# speedmeter_3_3reg.net
KiCad netlist of a schematic drawn in EAGLE
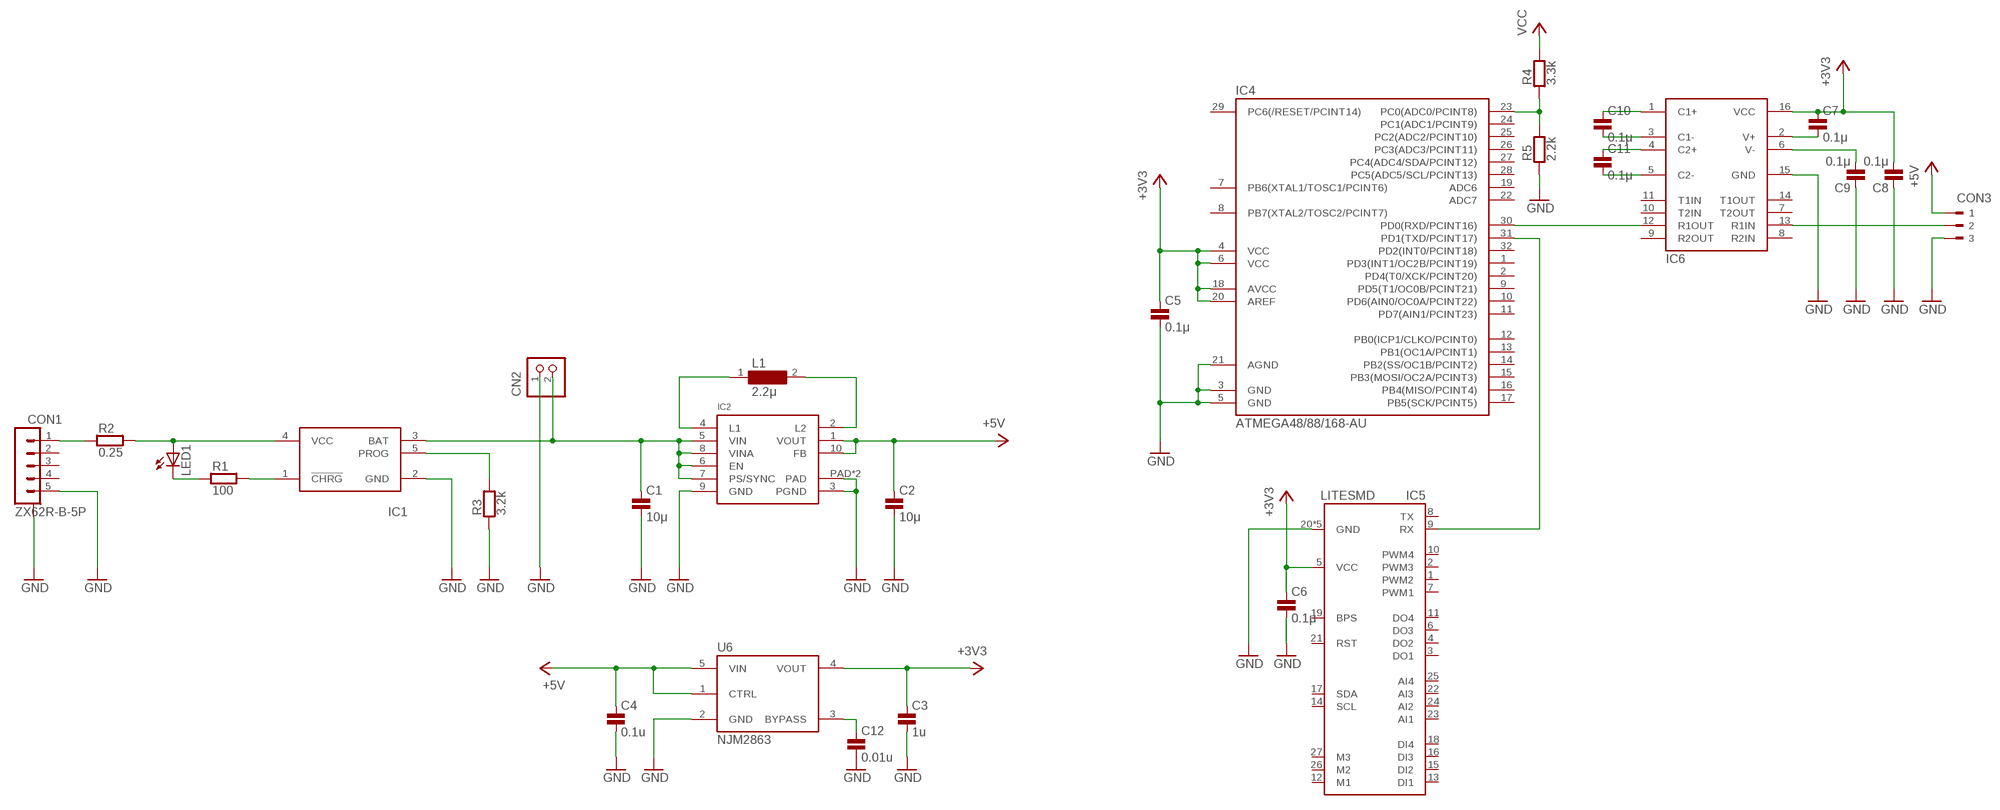
[diagram p0: schematic, sheet 1]

(export (version "E")
  (design (tool "Eeschema 10.0.6"))
  (components
    (comp (ref "C1")
      (value "10μ")
      (footprint "eagle-import:0603@1")
      (libsource (lib "eagle-import") (part "C0603"))
    )
    (comp (ref "C2")
      (value "10μ")
      (footprint "eagle-import:0603@1")
      (libsource (lib "eagle-import") (part "C0603"))
    )
    (comp (ref "C3")
      (value "1u")
      (footprint "eagle-import:0603@1")
      (libsource (lib "eagle-import") (part "C0603"))
    )
    (comp (ref "C4")
      (value "0.1u")
      (footprint "eagle-import:0603@1")
      (libsource (lib "eagle-import") (part "C0603"))
    )
    (comp (ref "C5")
      (value "0.1μ")
      (footprint "eagle-import:0603@1")
      (libsource (lib "eagle-import") (part "C0603"))
    )
    (comp (ref "C6")
      (value "0.1μ")
      (footprint "eagle-import:0603@1")
      (libsource (lib "eagle-import") (part "C0603"))
    )
    (comp (ref "C7")
      (value "0.1μ")
      (footprint "eagle-import:0603")
      (libsource (lib "eagle-import") (part "untitled-2_C0603"))
    )
    (comp (ref "C8")
      (value "0.1μ")
      (footprint "eagle-import:0603")
      (libsource (lib "eagle-import") (part "untitled-2_C0603"))
    )
    (comp (ref "C9")
      (value "0.1μ")
      (footprint "eagle-import:0603")
      (libsource (lib "eagle-import") (part "untitled-2_C0603"))
    )
    (comp (ref "C10")
      (value "0.1μ")
      (footprint "eagle-import:0603")
      (libsource (lib "eagle-import") (part "untitled-2_C0603"))
    )
    (comp (ref "C11")
      (value "0.1μ")
      (footprint "eagle-import:0603")
      (libsource (lib "eagle-import") (part "untitled-2_C0603"))
    )
    (comp (ref "C12")
      (value "0.01u")
      (footprint "eagle-import:0603@1")
      (libsource (lib "eagle-import") (part "C0603"))
    )
    (comp (ref "CN2")
      (value "S2B-PH-K-S")
      (footprint "eagle-import:S2B-PH-K-S")
      (libsource (lib "eagle-import") (part "S2B-PH-K-S"))
    )
    (comp (ref "CON1")
      (value "ZX62R-B-5P")
      (footprint "eagle-import:MICRO-B")
      (libsource (lib "eagle-import") (part "ZX62R-B-5P"))
    )
    (comp (ref "CON3")
      (value "180-3")
      (footprint "eagle-import:180-3")
      (libsource (lib "eagle-import") (part "180-3"))
    )
    (comp (ref "IC1")
      (value "LTC4054")
      (footprint "eagle-import:TSOT23-5")
      (libsource (lib "eagle-import") (part "LTC4054"))
    )
    (comp (ref "IC2")
      (value "TPS6300XDRCT")
      (footprint "eagle-import:S-PVSON-N10")
      (libsource (lib "eagle-import") (part "TPS6300XDRCT"))
    )
    (comp (ref "IC4")
      (value "ATMEGA48/88/168-AU")
      (footprint "eagle-import:TQFP32-08")
      (libsource (lib "eagle-import") (part "ATMEGA48/88/168-AU"))
    )
    (comp (ref "IC5")
      (value "LITESMD")
      (footprint "eagle-import:LITE")
      (libsource (lib "eagle-import") (part "LITESMD"))
    )
    (comp (ref "IC6")
      (value "ADM3202ARN")
      (footprint "eagle-import:SOP16")
      (libsource (lib "eagle-import") (part "ADM3202ARN"))
    )
    (comp (ref "L1")
      (value "2.2μ")
      (footprint "eagle-import:VLF4012ST")
      (libsource (lib "eagle-import") (part "VLF4012ST"))
    )
    (comp (ref "LED1")
      (value "LEDSML0603")
      (footprint "eagle-import:SML0603")
      (libsource (lib "eagle-import") (part "LEDSML0603"))
    )
    (comp (ref "R1")
      (value "100")
      (footprint "eagle-import:0603")
      (libsource (lib "eagle-import") (part "R0603"))
    )
    (comp (ref "R2")
      (value "0.25")
      (footprint "eagle-import:0603")
      (libsource (lib "eagle-import") (part "R0603"))
    )
    (comp (ref "R3")
      (value "3.2k")
      (footprint "eagle-import:0603")
      (libsource (lib "eagle-import") (part "R0603"))
    )
    (comp (ref "R4")
      (value "3.3k")
      (footprint "eagle-import:0603")
      (libsource (lib "eagle-import") (part "R0603"))
    )
    (comp (ref "R5")
      (value "2.2k")
      (footprint "eagle-import:0603")
      (libsource (lib "eagle-import") (part "R0603"))
    )
    (comp (ref "U6")
      (value "NJM2863")
      (footprint "eagle-import:SOT23_5PIN")
      (libsource (lib "eagle-import") (part "NJM2863"))
    )
  )
  (nets
    (net (code "1") (name "+3V3") (class "Default")
      (node (ref "C3") (pin "1") (pinfunction "P$1_1") (pintype "passive"))
      (node (ref "C5") (pin "1") (pinfunction "P$1_1") (pintype "passive"))
      (node (ref "C6") (pin "1") (pinfunction "P$1_1") (pintype "passive"))
      (node (ref "C7") (pin "1") (pinfunction "P$1_1") (pintype "passive"))
      (node (ref "C8") (pin "2") (pinfunction "P$2_2") (pintype "passive"))
      (node (ref "IC4") (pin "18") (pinfunction "AVCC_18") (pintype "passive"))
      (node (ref "IC4") (pin "20") (pinfunction "AREF_20") (pintype "passive"))
      (node (ref "IC4") (pin "4") (pinfunction "VCC_4") (pintype "power_in"))
      (node (ref "IC4") (pin "6") (pinfunction "VCC_6") (pintype "power_in"))
      (node (ref "IC5") (pin "5") (pinfunction "VCC_5") (pintype "power_in"))
      (node (ref "IC6") (pin "16") (pinfunction "VCC_16") (pintype "bidirectional"))
      (node (ref "U6") (pin "4") (pinfunction "VOUT_4") (pintype "output"))
    )
    (net (code "2") (name "+5V") (class "Default")
      (node (ref "C2") (pin "1") (pinfunction "P$1_1") (pintype "passive"))
      (node (ref "C4") (pin "1") (pinfunction "P$1_1") (pintype "passive"))
      (node (ref "CON3") (pin "1") (pinfunction "1_1") (pintype "passive"))
      (node (ref "IC2") (pin "1") (pinfunction "VOUT_1") (pintype "output"))
      (node (ref "IC2") (pin "10") (pinfunction "FB_10") (pintype "input"))
      (node (ref "U6") (pin "1") (pinfunction "CTRL_1") (pintype "input"))
      (node (ref "U6") (pin "5") (pinfunction "VIN_5") (pintype "input"))
    )
    (net (code "3") (name "GND") (class "Default")
      (node (ref "C1") (pin "2") (pinfunction "P$2_2") (pintype "passive"))
      (node (ref "C12") (pin "2") (pinfunction "P$2_2") (pintype "passive"))
      (node (ref "C2") (pin "2") (pinfunction "P$2_2") (pintype "passive"))
      (node (ref "C3") (pin "2") (pinfunction "P$2_2") (pintype "passive"))
      (node (ref "C4") (pin "2") (pinfunction "P$2_2") (pintype "passive"))
      (node (ref "C5") (pin "2") (pinfunction "P$2_2") (pintype "passive"))
      (node (ref "C6") (pin "2") (pinfunction "P$2_2") (pintype "passive"))
      (node (ref "C8") (pin "1") (pinfunction "P$1_1") (pintype "passive"))
      (node (ref "C9") (pin "1") (pinfunction "P$1_1") (pintype "passive"))
      (node (ref "CN2") (pin "1") (pinfunction "1_1") (pintype "passive"))
      (node (ref "CON1") (pin "5") (pinfunction "1.VBUS_5") (pintype "passive"))
      (node (ref "CON1") (pin "CASE@1") (pinfunction "P$1_CASE@1") (pintype "bidirectional"))
      (node (ref "CON1") (pin "CASE@2") (pinfunction "P$1_CASE@2") (pintype "bidirectional"))
      (node (ref "CON1") (pin "CASE@3") (pinfunction "P$1_CASE@3") (pintype "bidirectional"))
      (node (ref "CON1") (pin "CASE@4") (pinfunction "P$1_CASE@4") (pintype "bidirectional"))
      (node (ref "CON3") (pin "3") (pinfunction "3_3") (pintype "passive"))
      (node (ref "IC1") (pin "2") (pinfunction "GND_2") (pintype "power_in"))
      (node (ref "IC2") (pin "3") (pinfunction "PGND_3") (pintype "power_in"))
      (node (ref "IC2") (pin "9") (pinfunction "GND_9") (pintype "power_in"))
      (node (ref "IC2") (pin "PAD") (pinfunction "PAD_PAD") (pintype "power_in"))
      (node (ref "IC2") (pin "PAD@1") (pinfunction "PAD_PAD@1") (pintype "power_in"))
      (node (ref "IC4") (pin "21") (pinfunction "AGND_21") (pintype "power_in"))
      (node (ref "IC4") (pin "3") (pinfunction "GND_3") (pintype "power_in"))
      (node (ref "IC4") (pin "5") (pinfunction "GND_5") (pintype "power_in"))
      (node (ref "IC5") (pin "20") (pinfunction "GND_20") (pintype "power_in"))
      (node (ref "IC5") (pin "28") (pinfunction "GND_28") (pintype "power_in"))
      (node (ref "IC5") (pin "30") (pinfunction "GND_30") (pintype "power_in"))
      (node (ref "IC5") (pin "31") (pinfunction "GND_31") (pintype "power_in"))
      (node (ref "IC5") (pin "32") (pinfunction "GND_32") (pintype "power_in"))
      (node (ref "IC6") (pin "15") (pinfunction "GND_15") (pintype "bidirectional"))
      (node (ref "R3") (pin "1") (pinfunction "P$1_1") (pintype "passive"))
      (node (ref "R5") (pin "1") (pinfunction "P$1_1") (pintype "passive"))
      (node (ref "U6") (pin "2") (pinfunction "GND_2") (pintype "power_in"))
    )
    (net (code "4") (name "Net-(C7-P$2)") (class "Default")
      (node (ref "C7") (pin "2") (pinfunction "P$2_2") (pintype "passive"))
      (node (ref "IC6") (pin "2") (pinfunction "V+_2") (pintype "bidirectional"))
    )
    (net (code "5") (name "Net-(C9-P$2)") (class "Default")
      (node (ref "C9") (pin "2") (pinfunction "P$2_2") (pintype "passive"))
      (node (ref "IC6") (pin "6") (pinfunction "V-_6") (pintype "bidirectional"))
    )
    (net (code "6") (name "Net-(C10-P$1)") (class "Default")
      (node (ref "C10") (pin "1") (pinfunction "P$1_1") (pintype "passive"))
      (node (ref "IC6") (pin "1") (pinfunction "C1+_1") (pintype "bidirectional"))
    )
    (net (code "7") (name "Net-(C10-P$2)") (class "Default")
      (node (ref "C10") (pin "2") (pinfunction "P$2_2") (pintype "passive"))
      (node (ref "IC6") (pin "3") (pinfunction "C1-_3") (pintype "bidirectional"))
    )
    (net (code "8") (name "Net-(C11-P$1)") (class "Default")
      (node (ref "C11") (pin "1") (pinfunction "P$1_1") (pintype "passive"))
      (node (ref "IC6") (pin "4") (pinfunction "C2+_4") (pintype "bidirectional"))
    )
    (net (code "9") (name "Net-(C11-P$2)") (class "Default")
      (node (ref "C11") (pin "2") (pinfunction "P$2_2") (pintype "passive"))
      (node (ref "IC6") (pin "5") (pinfunction "C2-_5") (pintype "bidirectional"))
    )
    (net (code "10") (name "Net-(C12-P$1)") (class "Default")
      (node (ref "C12") (pin "1") (pinfunction "P$1_1") (pintype "passive"))
      (node (ref "U6") (pin "3") (pinfunction "BYPASS_3") (pintype "passive"))
    )
    (net (code "11") (name "Net-(CON1-5.GND)") (class "Default")
      (node (ref "CON1") (pin "1") (pinfunction "5.GND_1") (pintype "passive"))
      (node (ref "R2") (pin "1") (pinfunction "P$1_1") (pintype "passive"))
    )
    (net (code "12") (name "Net-(IC1-PROG)") (class "Default")
      (node (ref "IC1") (pin "5") (pinfunction "PROG_5") (pintype "passive"))
      (node (ref "R3") (pin "2") (pinfunction "P$2_2") (pintype "passive"))
    )
    (net (code "13") (name "Net-(IC1-VCC)") (class "Default")
      (node (ref "IC1") (pin "4") (pinfunction "VCC_4") (pintype "power_in"))
      (node (ref "LED1") (pin "A") (pinfunction "A_A") (pintype "passive"))
      (node (ref "R2") (pin "2") (pinfunction "P$2_2") (pintype "passive"))
    )
    (net (code "14") (name "Net-(IC1-~{CHRG})") (class "Default")
      (node (ref "IC1") (pin "1") (pinfunction "~{CHRG}_1") (pintype "output"))
      (node (ref "R1") (pin "2") (pinfunction "P$2_2") (pintype "passive"))
    )
    (net (code "15") (name "Net-(IC2-L1)") (class "Default")
      (node (ref "IC2") (pin "4") (pinfunction "L1_4") (pintype "bidirectional"))
      (node (ref "L1") (pin "1") (pinfunction "1_1") (pintype "passive"))
    )
    (net (code "16") (name "Net-(IC2-L2)") (class "Default")
      (node (ref "IC2") (pin "2") (pinfunction "L2_2") (pintype "bidirectional"))
      (node (ref "L1") (pin "2") (pinfunction "2_2") (pintype "passive"))
    )
    (net (code "17") (name "Net-(IC4-PC0(ADC0{slash}PCINT8))") (class "Default")
      (node (ref "IC4") (pin "23") (pinfunction "PC0(ADC0/PCINT8)_23") (pintype "bidirectional"))
      (node (ref "R4") (pin "1") (pinfunction "P$1_1") (pintype "passive"))
      (node (ref "R5") (pin "2") (pinfunction "P$2_2") (pintype "passive"))
    )
    (net (code "18") (name "Net-(IC4-PD0(RXD{slash}PCINT16))") (class "Default")
      (node (ref "IC4") (pin "30") (pinfunction "PD0(RXD/PCINT16)_30") (pintype "bidirectional"))
      (node (ref "IC6") (pin "12") (pinfunction "R1OUT_12") (pintype "bidirectional"))
    )
    (net (code "19") (name "Net-(IC4-PD1(TXD{slash}PCINT17))") (class "Default")
      (node (ref "IC4") (pin "31") (pinfunction "PD1(TXD/PCINT17)_31") (pintype "bidirectional"))
      (node (ref "IC5") (pin "9") (pinfunction "RX_9") (pintype "input"))
    )
    (net (code "20") (name "Net-(IC6-R1IN)") (class "Default")
      (node (ref "CON3") (pin "2") (pinfunction "2_2") (pintype "passive"))
      (node (ref "IC6") (pin "13") (pinfunction "R1IN_13") (pintype "bidirectional"))
    )
    (net (code "21") (name "Net-(R1-P$1)") (class "Default")
      (node (ref "LED1") (pin "C") (pinfunction "C_C") (pintype "passive"))
      (node (ref "R1") (pin "1") (pinfunction "P$1_1") (pintype "passive"))
    )
    (net (code "22") (name "VCC") (class "Default")
      (node (ref "C1") (pin "1") (pinfunction "P$1_1") (pintype "passive"))
      (node (ref "CN2") (pin "2") (pinfunction "2_2") (pintype "passive"))
      (node (ref "IC1") (pin "3") (pinfunction "BAT_3") (pintype "power_in"))
      (node (ref "IC2") (pin "5") (pinfunction "VIN_5") (pintype "power_in"))
      (node (ref "IC2") (pin "6") (pinfunction "EN_6") (pintype "input"))
      (node (ref "IC2") (pin "7") (pinfunction "PS/SYNC_7") (pintype "input"))
      (node (ref "IC2") (pin "8") (pinfunction "VINA_8") (pintype "power_in"))
      (node (ref "R4") (pin "2") (pinfunction "P$2_2") (pintype "passive"))
    )
    (net (code "23") (name "unconnected-(CON1-2.D--Pad4)") (class "Default")
      (node (ref "CON1") (pin "4") (pinfunction "2.D-_4") (pintype "passive"))
    )
    (net (code "24") (name "unconnected-(CON1-3.D+-Pad3)") (class "Default")
      (node (ref "CON1") (pin "3") (pinfunction "3.D+_3") (pintype "passive"))
    )
    (net (code "25") (name "unconnected-(CON1-4.ID-Pad2)") (class "Default")
      (node (ref "CON1") (pin "2") (pinfunction "4.ID_2") (pintype "passive"))
    )
    (net (code "26") (name "unconnected-(IC4-ADC6-Pad19)") (class "Default")
      (node (ref "IC4") (pin "19") (pinfunction "ADC6_19") (pintype "passive"))
    )
    (net (code "27") (name "unconnected-(IC4-ADC7-Pad22)") (class "Default")
      (node (ref "IC4") (pin "22") (pinfunction "ADC7_22") (pintype "passive"))
    )
    (net (code "28") (name "unconnected-(IC4-PB0(ICP1{slash}CLKO{slash}PCINT0)-Pad12)") (class "Default")
      (node (ref "IC4") (pin "12") (pinfunction "PB0(ICP1/CLKO/PCINT0)_12") (pintype "bidirectional"))
    )
    (net (code "29") (name "unconnected-(IC4-PB1(OC1A{slash}PCINT1)-Pad13)") (class "Default")
      (node (ref "IC4") (pin "13") (pinfunction "PB1(OC1A/PCINT1)_13") (pintype "bidirectional"))
    )
    (net (code "30") (name "unconnected-(IC4-PB2(SS{slash}OC1B{slash}PCINT2)-Pad14)") (class "Default")
      (node (ref "IC4") (pin "14") (pinfunction "PB2(SS/OC1B/PCINT2)_14") (pintype "bidirectional"))
    )
    (net (code "31") (name "unconnected-(IC4-PB3(MOSI{slash}OC2A{slash}PCINT3)-Pad15)") (class "Default")
      (node (ref "IC4") (pin "15") (pinfunction "PB3(MOSI/OC2A/PCINT3)_15") (pintype "bidirectional"))
    )
    (net (code "32") (name "unconnected-(IC4-PB4(MISO{slash}PCINT4)-Pad16)") (class "Default")
      (node (ref "IC4") (pin "16") (pinfunction "PB4(MISO/PCINT4)_16") (pintype "bidirectional"))
    )
    (net (code "33") (name "unconnected-(IC4-PB5(SCK{slash}PCINT5)-Pad17)") (class "Default")
      (node (ref "IC4") (pin "17") (pinfunction "PB5(SCK/PCINT5)_17") (pintype "bidirectional"))
    )
    (net (code "34") (name "unconnected-(IC4-PB6(XTAL1{slash}TOSC1{slash}PCINT6)-Pad7)") (class "Default")
      (node (ref "IC4") (pin "7") (pinfunction "PB6(XTAL1/TOSC1/PCINT6)_7") (pintype "bidirectional"))
    )
    (net (code "35") (name "unconnected-(IC4-PB7(XTAL2{slash}TOSC2{slash}PCINT7)-Pad8)") (class "Default")
      (node (ref "IC4") (pin "8") (pinfunction "PB7(XTAL2/TOSC2/PCINT7)_8") (pintype "bidirectional"))
    )
    (net (code "36") (name "unconnected-(IC4-PC1(ADC1{slash}PCINT9)-Pad24)") (class "Default")
      (node (ref "IC4") (pin "24") (pinfunction "PC1(ADC1/PCINT9)_24") (pintype "bidirectional"))
    )
    (net (code "37") (name "unconnected-(IC4-PC2(ADC2{slash}PCINT10)-Pad25)") (class "Default")
      (node (ref "IC4") (pin "25") (pinfunction "PC2(ADC2/PCINT10)_25") (pintype "bidirectional"))
    )
    (net (code "38") (name "unconnected-(IC4-PC3(ADC3{slash}PCINT11)-Pad26)") (class "Default")
      (node (ref "IC4") (pin "26") (pinfunction "PC3(ADC3/PCINT11)_26") (pintype "bidirectional"))
    )
    (net (code "39") (name "unconnected-(IC4-PC4(ADC4{slash}SDA{slash}PCINT12)-Pad27)") (class "Default")
      (node (ref "IC4") (pin "27") (pinfunction "PC4(ADC4/SDA/PCINT12)_27") (pintype "bidirectional"))
    )
    (net (code "40") (name "unconnected-(IC4-PC5(ADC5{slash}SCL{slash}PCINT13)-Pad28)") (class "Default")
      (node (ref "IC4") (pin "28") (pinfunction "PC5(ADC5/SCL/PCINT13)_28") (pintype "bidirectional"))
    )
    (net (code "41") (name "unconnected-(IC4-PC6({slash}RESET{slash}PCINT14)-Pad29)") (class "Default")
      (node (ref "IC4") (pin "29") (pinfunction "PC6(/RESET/PCINT14)_29") (pintype "bidirectional"))
    )
    (net (code "42") (name "unconnected-(IC4-PD2(INT0{slash}PCINT18)-Pad32)") (class "Default")
      (node (ref "IC4") (pin "32") (pinfunction "PD2(INT0/PCINT18)_32") (pintype "bidirectional"))
    )
    (net (code "43") (name "unconnected-(IC4-PD3(INT1{slash}OC2B{slash}PCINT19)-Pad1)") (class "Default")
      (node (ref "IC4") (pin "1") (pinfunction "PD3(INT1/OC2B/PCINT19)_1") (pintype "bidirectional"))
    )
    (net (code "44") (name "unconnected-(IC4-PD4(T0{slash}XCK{slash}PCINT20)-Pad2)") (class "Default")
      (node (ref "IC4") (pin "2") (pinfunction "PD4(T0/XCK/PCINT20)_2") (pintype "bidirectional"))
    )
    (net (code "45") (name "unconnected-(IC4-PD5(T1{slash}OC0B{slash}PCINT21)-Pad9)") (class "Default")
      (node (ref "IC4") (pin "9") (pinfunction "PD5(T1/OC0B/PCINT21)_9") (pintype "bidirectional"))
    )
    (net (code "46") (name "unconnected-(IC4-PD6(AIN0{slash}OC0A{slash}PCINT22)-Pad10)") (class "Default")
      (node (ref "IC4") (pin "10") (pinfunction "PD6(AIN0/OC0A/PCINT22)_10") (pintype "bidirectional"))
    )
    (net (code "47") (name "unconnected-(IC4-PD7(AIN1{slash}PCINT23)-Pad11)") (class "Default")
      (node (ref "IC4") (pin "11") (pinfunction "PD7(AIN1/PCINT23)_11") (pintype "bidirectional"))
    )
    (net (code "48") (name "unconnected-(IC5-AI1-Pad23)") (class "Default")
      (node (ref "IC5") (pin "23") (pinfunction "AI1_23") (pintype "input"))
    )
    (net (code "49") (name "unconnected-(IC5-AI2-Pad24)") (class "Default")
      (node (ref "IC5") (pin "24") (pinfunction "AI2_24") (pintype "input"))
    )
    (net (code "50") (name "unconnected-(IC5-AI3-Pad22)") (class "Default")
      (node (ref "IC5") (pin "22") (pinfunction "AI3_22") (pintype "input"))
    )
    (net (code "51") (name "unconnected-(IC5-AI4-Pad25)") (class "Default")
      (node (ref "IC5") (pin "25") (pinfunction "AI4_25") (pintype "input"))
    )
    (net (code "52") (name "unconnected-(IC5-BPS-Pad19)") (class "Default")
      (node (ref "IC5") (pin "19") (pinfunction "BPS_19") (pintype "input"))
    )
    (net (code "53") (name "unconnected-(IC5-DI1-Pad13)") (class "Default")
      (node (ref "IC5") (pin "13") (pinfunction "DI1_13") (pintype "input"))
    )
    (net (code "54") (name "unconnected-(IC5-DI2-Pad15)") (class "Default")
      (node (ref "IC5") (pin "15") (pinfunction "DI2_15") (pintype "input"))
    )
    (net (code "55") (name "unconnected-(IC5-DI3-Pad16)") (class "Default")
      (node (ref "IC5") (pin "16") (pinfunction "DI3_16") (pintype "input"))
    )
    (net (code "56") (name "unconnected-(IC5-DI4-Pad18)") (class "Default")
      (node (ref "IC5") (pin "18") (pinfunction "DI4_18") (pintype "input"))
    )
    (net (code "57") (name "unconnected-(IC5-DO1-Pad3)") (class "Default")
      (node (ref "IC5") (pin "3") (pinfunction "DO1_3") (pintype "output"))
    )
    (net (code "58") (name "unconnected-(IC5-DO2-Pad4)") (class "Default")
      (node (ref "IC5") (pin "4") (pinfunction "DO2_4") (pintype "output"))
    )
    (net (code "59") (name "unconnected-(IC5-DO3-Pad6)") (class "Default")
      (node (ref "IC5") (pin "6") (pinfunction "DO3_6") (pintype "output"))
    )
    (net (code "60") (name "unconnected-(IC5-DO4-Pad11)") (class "Default")
      (node (ref "IC5") (pin "11") (pinfunction "DO4_11") (pintype "output"))
    )
    (net (code "61") (name "unconnected-(IC5-M1-Pad12)") (class "Default")
      (node (ref "IC5") (pin "12") (pinfunction "M1_12") (pintype "input"))
    )
    (net (code "62") (name "unconnected-(IC5-M2-Pad26)") (class "Default")
      (node (ref "IC5") (pin "26") (pinfunction "M2_26") (pintype "input"))
    )
    (net (code "63") (name "unconnected-(IC5-M3-Pad27)") (class "Default")
      (node (ref "IC5") (pin "27") (pinfunction "M3_27") (pintype "input"))
    )
    (net (code "64") (name "unconnected-(IC5-PWM1-Pad7)") (class "Default")
      (node (ref "IC5") (pin "7") (pinfunction "PWM1_7") (pintype "output"))
    )
    (net (code "65") (name "unconnected-(IC5-PWM2-Pad1)") (class "Default")
      (node (ref "IC5") (pin "1") (pinfunction "PWM2_1") (pintype "output"))
    )
    (net (code "66") (name "unconnected-(IC5-PWM3-Pad2)") (class "Default")
      (node (ref "IC5") (pin "2") (pinfunction "PWM3_2") (pintype "output"))
    )
    (net (code "67") (name "unconnected-(IC5-PWM4-Pad10)") (class "Default")
      (node (ref "IC5") (pin "10") (pinfunction "PWM4_10") (pintype "output"))
    )
    (net (code "68") (name "unconnected-(IC5-RST-Pad21)") (class "Default")
      (node (ref "IC5") (pin "21") (pinfunction "RST_21") (pintype "input"))
    )
    (net (code "69") (name "unconnected-(IC5-SCL-Pad14)") (class "Default")
      (node (ref "IC5") (pin "14") (pinfunction "SCL_14") (pintype "bidirectional"))
    )
    (net (code "70") (name "unconnected-(IC5-SDA-Pad17)") (class "Default")
      (node (ref "IC5") (pin "17") (pinfunction "SDA_17") (pintype "bidirectional"))
    )
    (net (code "71") (name "unconnected-(IC5-TX-Pad8)") (class "Default")
      (node (ref "IC5") (pin "8") (pinfunction "TX_8") (pintype "output"))
    )
    (net (code "72") (name "unconnected-(IC6-R2IN-Pad8)") (class "Default")
      (node (ref "IC6") (pin "8") (pinfunction "R2IN_8") (pintype "bidirectional"))
    )
    (net (code "73") (name "unconnected-(IC6-R2OUT-Pad9)") (class "Default")
      (node (ref "IC6") (pin "9") (pinfunction "R2OUT_9") (pintype "bidirectional"))
    )
    (net (code "74") (name "unconnected-(IC6-T1IN-Pad11)") (class "Default")
      (node (ref "IC6") (pin "11") (pinfunction "T1IN_11") (pintype "bidirectional"))
    )
    (net (code "75") (name "unconnected-(IC6-T1OUT-Pad14)") (class "Default")
      (node (ref "IC6") (pin "14") (pinfunction "T1OUT_14") (pintype "bidirectional"))
    )
    (net (code "76") (name "unconnected-(IC6-T2IN-Pad10)") (class "Default")
      (node (ref "IC6") (pin "10") (pinfunction "T2IN_10") (pintype "bidirectional"))
    )
    (net (code "77") (name "unconnected-(IC6-T2OUT-Pad7)") (class "Default")
      (node (ref "IC6") (pin "7") (pinfunction "T2OUT_7") (pintype "bidirectional"))
    )
  )
)
